# HARE_-_3PDT_Breakout_Schematic_v1_0.net
KiCad netlist of a schematic drawn in EAGLE
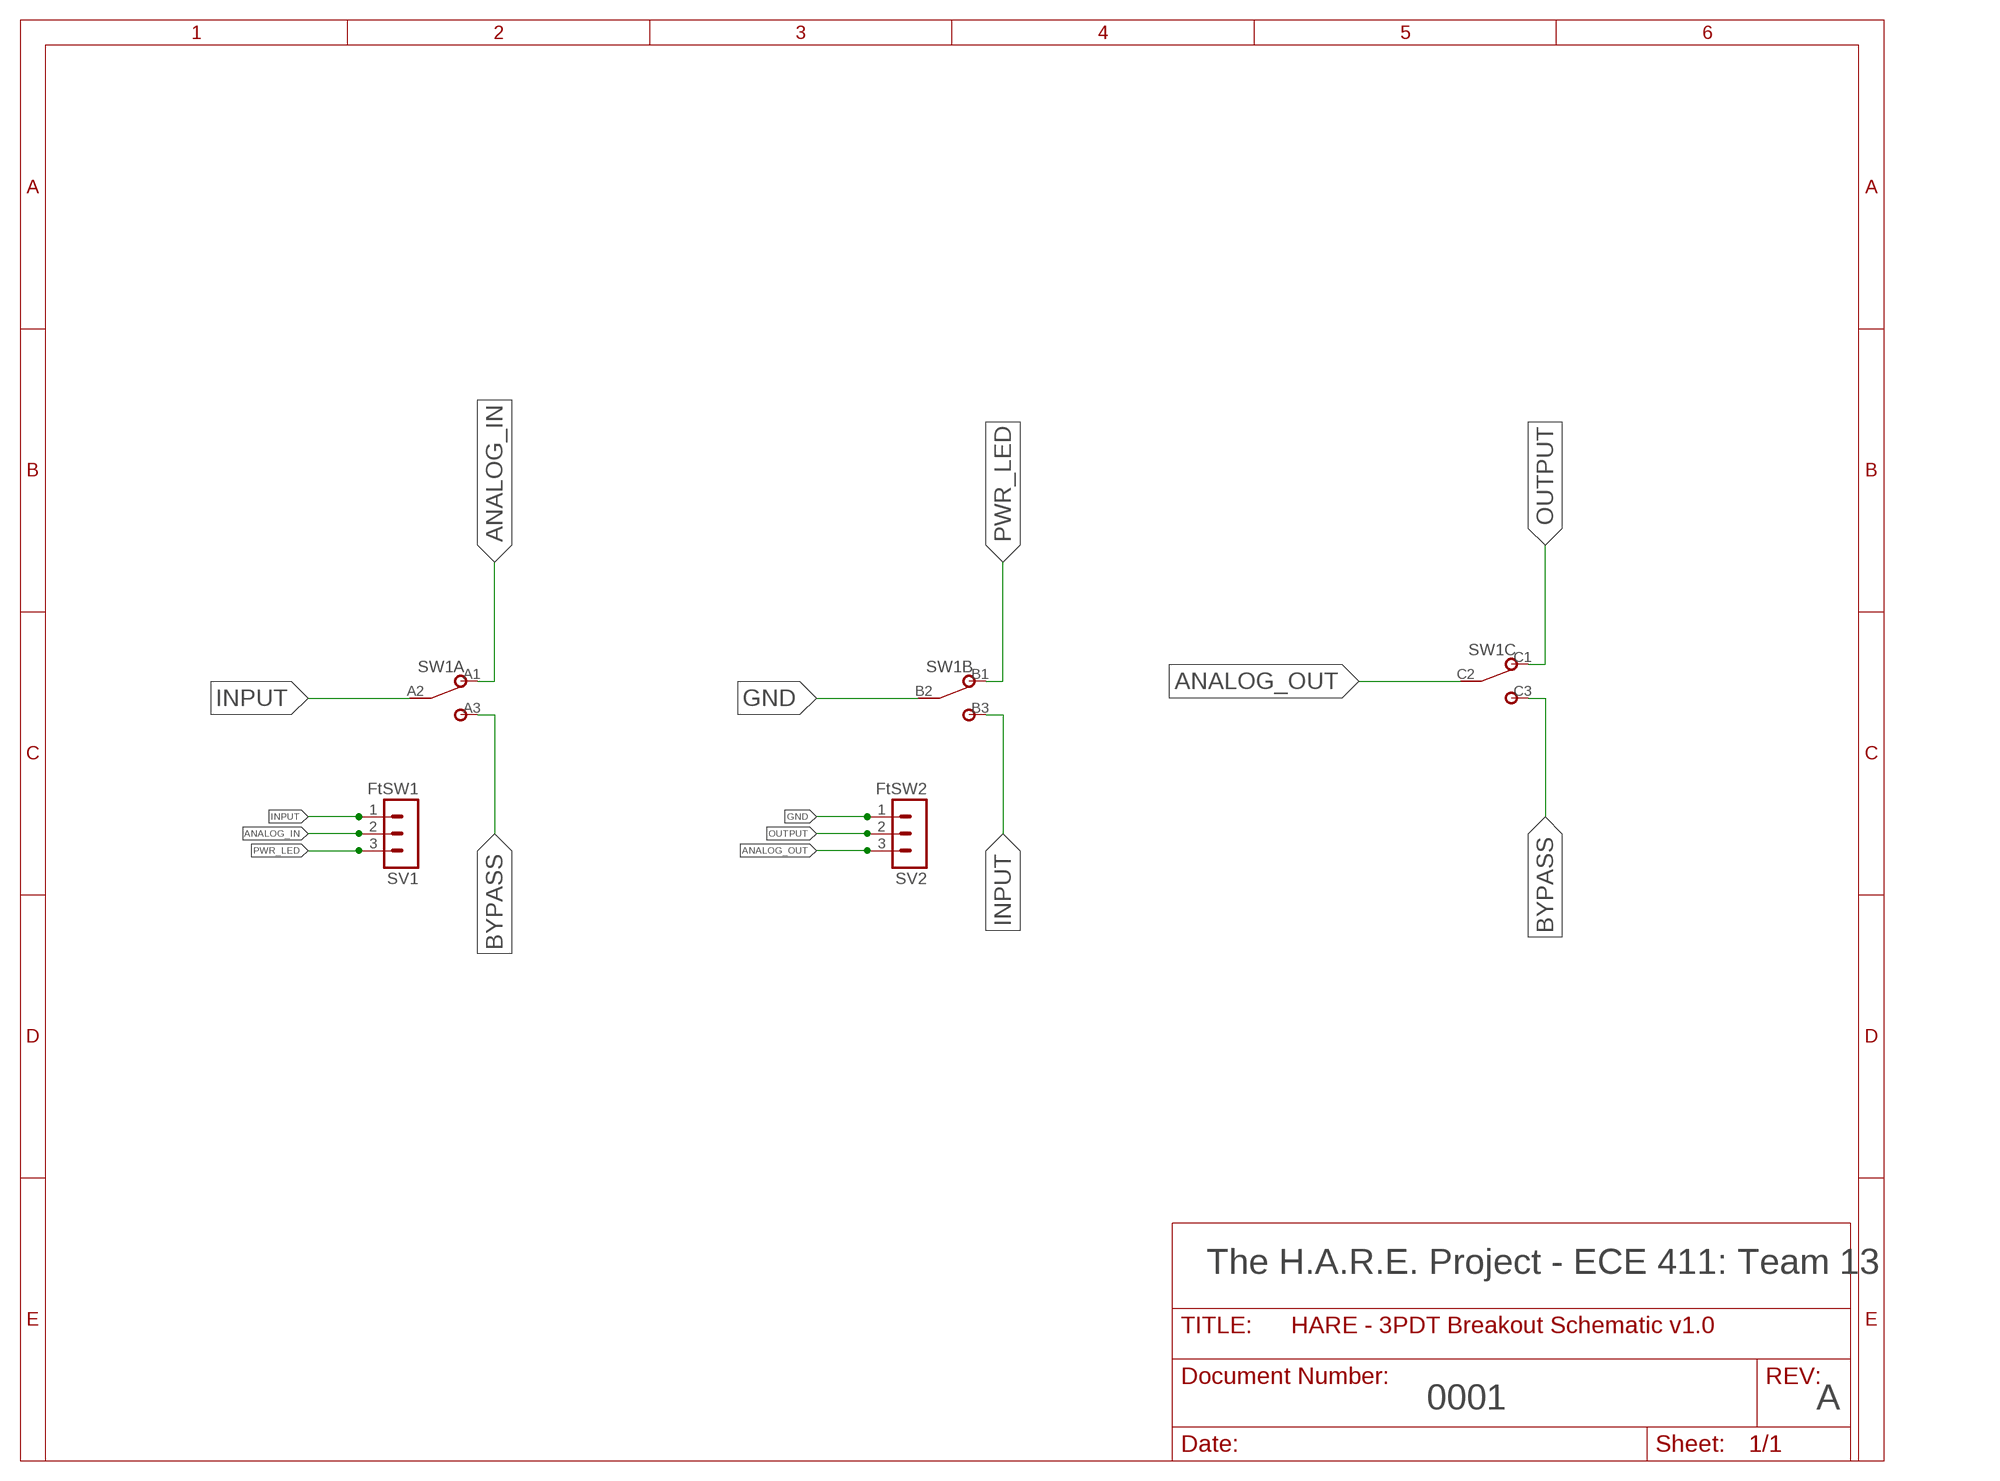
[diagram p0: schematic, sheet 1]

(export (version "E")
  (design (tool "Eeschema 10.0.6"))
  (components
    (comp (ref "SV1")
      (value "FtSW1")
      (footprint "eagle-import:MA03-1")
      (libsource (lib "eagle-import") (part "MA03-1"))
    )
    (comp (ref "SV2")
      (value "FtSW2")
      (footprint "eagle-import:MA03-1")
      (libsource (lib "eagle-import") (part "MA03-1"))
    )
    (comp (ref "SW1")
      (value "3PDTBLUE")
      (footprint "eagle-import:CHINABLUE")
      (libsource (lib "eagle-import") (part "3PDTBLUE"))
    )
  )
  (nets
    (net (code "1") (name "ANALOG_IN") (class "Default")
      (node (ref "SV1") (pin "2") (pinfunction "2_2") (pintype "passive"))
      (node (ref "SW1") (pin "A1") (pinfunction "1_A1") (pintype "passive"))
    )
    (net (code "2") (name "ANALOG_OUT") (class "Default")
      (node (ref "SV2") (pin "3") (pinfunction "3_3") (pintype "passive"))
      (node (ref "SW1") (pin "C2") (pinfunction "2_C2") (pintype "passive"))
    )
    (net (code "3") (name "BYPASS") (class "Default")
      (node (ref "SW1") (pin "A3") (pinfunction "3_A3") (pintype "passive"))
      (node (ref "SW1") (pin "C3") (pinfunction "3_C3") (pintype "passive"))
    )
    (net (code "4") (name "GND") (class "Default")
      (node (ref "SV2") (pin "1") (pinfunction "1_1") (pintype "passive"))
      (node (ref "SW1") (pin "B2") (pinfunction "2_B2") (pintype "passive"))
    )
    (net (code "5") (name "INPUT") (class "Default")
      (node (ref "SV1") (pin "1") (pinfunction "1_1") (pintype "passive"))
      (node (ref "SW1") (pin "A2") (pinfunction "2_A2") (pintype "passive"))
      (node (ref "SW1") (pin "B3") (pinfunction "3_B3") (pintype "passive"))
    )
    (net (code "6") (name "OUTPUT") (class "Default")
      (node (ref "SV2") (pin "2") (pinfunction "2_2") (pintype "passive"))
      (node (ref "SW1") (pin "C1") (pinfunction "1_C1") (pintype "passive"))
    )
    (net (code "7") (name "PWR_LED") (class "Default")
      (node (ref "SV1") (pin "3") (pinfunction "3_3") (pintype "passive"))
      (node (ref "SW1") (pin "B1") (pinfunction "1_B1") (pintype "passive"))
    )
  )
)
